# Top_Level.net
KiCad netlist of a schematic drawn in Altium Designer
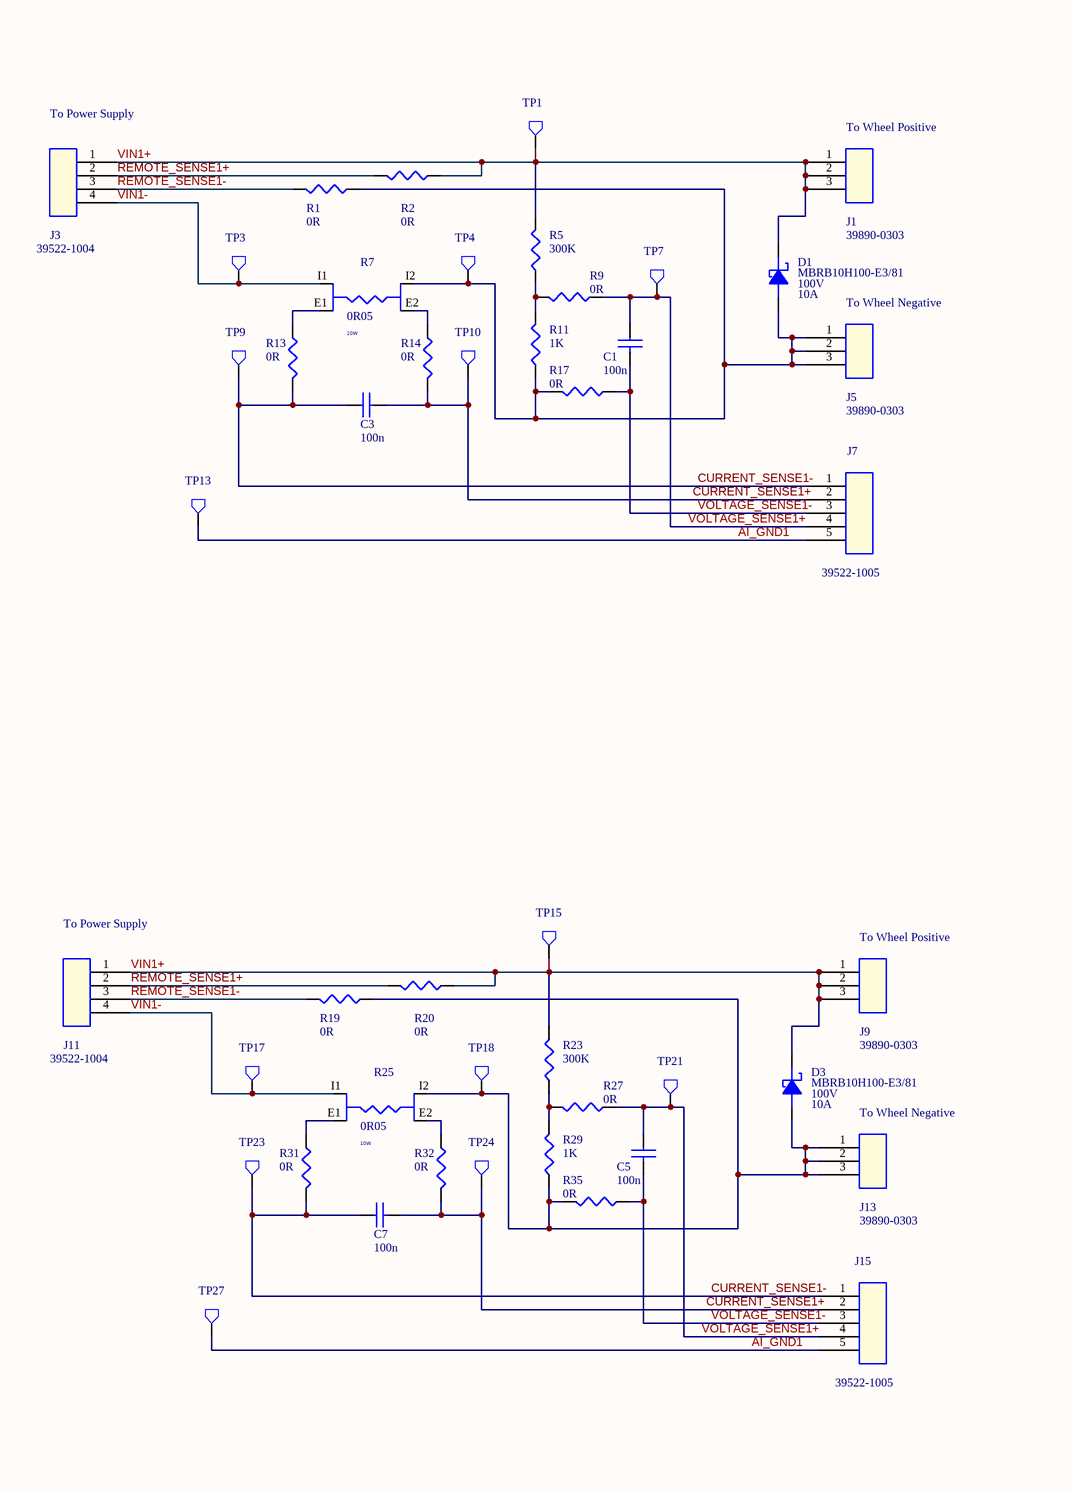
[diagram p0: Top Level.SchDoc, left]
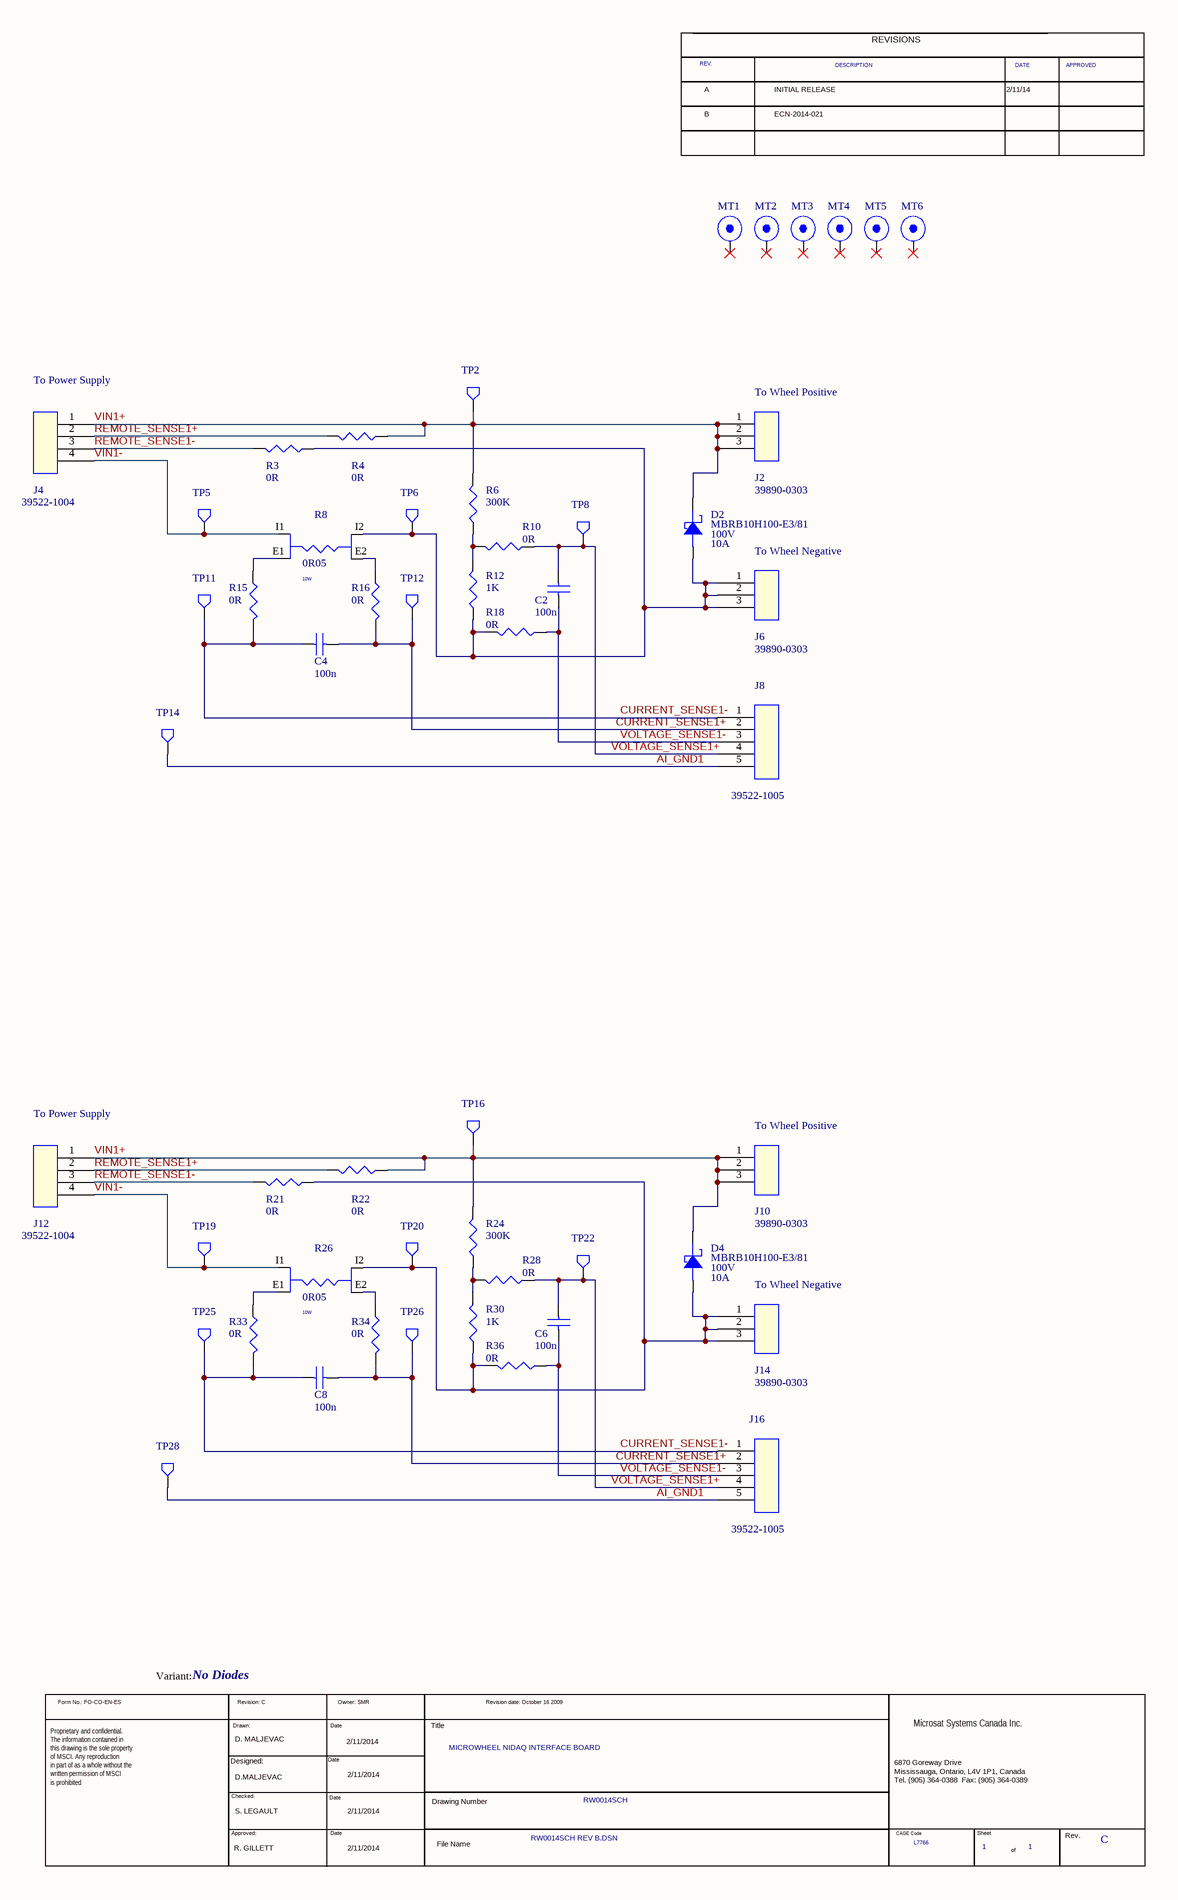
[diagram p1: Top Level.SchDoc, right]

(export (version "E")
  (design (tool "Eeschema 10.0.6"))
  (components
    (comp (ref "C1")
      (value "100n")
      (footprint "C.0805")
      (description "Film Capacitors .1uF 250volt 5%")
      (fields (field (name "PART NUMBER") "MKP1841410254") (field (name "MANUFACTURER") "Kemet"))
      (libsource (lib "*") (part "MIL-PRF-55681 - Cap, Cer"))
    )
    (comp (ref "C2")
      (value "100n")
      (footprint "C.0805")
      (description "Film Capacitors .1uF 250volt 5%")
      (fields (field (name "PART NUMBER") "MKP1841410254") (field (name "MANUFACTURER") "Kemet"))
      (libsource (lib "*") (part "MIL-PRF-55681 - Cap, Cer"))
    )
    (comp (ref "C3")
      (value "100n")
      (footprint "C.0805")
      (description "Film Capacitors .1uF 250volt 5%")
      (fields (field (name "MANUFACTURER") "Vishay") (field (name "TOLERANCE") "5%"))
      (libsource (lib "*") (part "MIL-PRF-55681 - Cap, Cer"))
    )
    (comp (ref "C4")
      (value "100n")
      (footprint "C.0805")
      (description "Film Capacitors .1uF 250volt 5%")
      (fields (field (name "MANUFACTURER") "Vishay") (field (name "TOLERANCE") "5%"))
      (libsource (lib "*") (part "MIL-PRF-55681 - Cap, Cer"))
    )
    (comp (ref "C5")
      (value "100n")
      (footprint "C.0805")
      (description "Film Capacitors .1uF 250volt 5%")
      (fields (field (name "PART NUMBER") "MKP1841410254") (field (name "MANUFACTURER") "Kemet"))
      (libsource (lib "*") (part "MIL-PRF-55681 - Cap, Cer"))
    )
    (comp (ref "C6")
      (value "100n")
      (footprint "C.0805")
      (description "Film Capacitors .1uF 250volt 5%")
      (fields (field (name "PART NUMBER") "MKP1841410254") (field (name "MANUFACTURER") "Kemet"))
      (libsource (lib "*") (part "MIL-PRF-55681 - Cap, Cer"))
    )
    (comp (ref "C7")
      (value "100n")
      (footprint "C.0805")
      (description "Film Capacitors .1uF 250volt 5%")
      (fields (field (name "MANUFACTURER") "Vishay") (field (name "TOLERANCE") "5%"))
      (libsource (lib "*") (part "MIL-PRF-55681 - Cap, Cer"))
    )
    (comp (ref "C8")
      (value "100n")
      (footprint "C.0805")
      (description "Film Capacitors .1uF 250volt 5%")
      (fields (field (name "MANUFACTURER") "Vishay") (field (name "TOLERANCE") "5%"))
      (libsource (lib "*") (part "MIL-PRF-55681 - Cap, Cer"))
    )
    (comp (ref "D1")
      (value "MBRB10H100-E3/81")
      (description "DIODE SCHOTTKY 100V 10A TO236AB")
      (fields
        (field (name "MANUFACTURER") "Vishay Semiconductor")
        (field (name "CURRENT") "10A")
        (field (name "VOLTAGE") "100V")
      )
      (libsource (lib "RW00014SCH REV B_Library") (part "DIODE SCHOTTKY"))
    )
    (comp (ref "D2")
      (value "MBRB10H100-E3/81")
      (description "DIODE SCHOTTKY 100V 10A TO236AB")
      (fields
        (field (name "MANUFACTURER") "Vishay Semiconductor")
        (field (name "CURRENT") "10A")
        (field (name "VOLTAGE") "100V")
      )
      (libsource (lib "RW00014SCH REV B_Library") (part "DIODE SCHOTTKY"))
    )
    (comp (ref "D3")
      (value "MBRB10H100-E3/81")
      (description "DIODE SCHOTTKY 100V 10A TO236AB")
      (fields
        (field (name "MANUFACTURER") "Vishay Semiconductor")
        (field (name "CURRENT") "10A")
        (field (name "VOLTAGE") "100V")
      )
      (libsource (lib "RW00014SCH REV B_Library") (part "DIODE SCHOTTKY"))
    )
    (comp (ref "D4")
      (value "MBRB10H100-E3/81")
      (description "DIODE SCHOTTKY 100V 10A TO236AB")
      (fields
        (field (name "MANUFACTURER") "Vishay Semiconductor")
        (field (name "CURRENT") "10A")
        (field (name "VOLTAGE") "100V")
      )
      (libsource (lib "RW00014SCH REV B_Library") (part "DIODE SCHOTTKY"))
    )
    (comp (ref "J1")
      (value "39890-0303")
      (footprint "CONN.39890-0303")
      (description "CONN, SCREW TERMINAL BLOCK, 3 POS, 5MM SPACING, TH")
      (fields (field (name "MANUFACTURER") "Molex"))
      (libsource (lib "*") (part "CON3"))
    )
    (comp (ref "J2")
      (value "39890-0303")
      (footprint "CONN.39890-0303")
      (description "CONN, SCREW TERMINAL BLOCK, 3 POS, 5MM SPACING, TH")
      (fields (field (name "MANUFACTURER") "Molex"))
      (libsource (lib "*") (part "CON3"))
    )
    (comp (ref "J3")
      (value "39522-1004")
      (footprint "CONN.39522-1004")
      (description "CONN, TERMINAL BLOCK HEADER, 4 POS, RIGHT ANGLE, 5MM SPACING, TH")
      (fields (field (name "MANUFACTURER") "Molex"))
      (libsource (lib "*") (part "CON4"))
    )
    (comp (ref "J4")
      (value "39522-1004")
      (footprint "CONN.39522-1004")
      (description "CONN, TERMINAL BLOCK HEADER, 4 POS, RIGHT ANGLE, 5MM SPACING, TH")
      (fields (field (name "MANUFACTURER") "Molex"))
      (libsource (lib "*") (part "CON4"))
    )
    (comp (ref "J5")
      (value "39890-0303")
      (footprint "CONN.39890-0303")
      (description "CONN, SCREW TERMINAL BLOCK, 3 POS, 5MM SPACING, TH")
      (fields (field (name "MANUFACTURER") "Molex"))
      (libsource (lib "*") (part "CON3"))
    )
    (comp (ref "J6")
      (value "39890-0303")
      (footprint "CONN.39890-0303")
      (description "CONN, SCREW TERMINAL BLOCK, 3 POS, 5MM SPACING, TH")
      (fields (field (name "MANUFACTURER") "Molex"))
      (libsource (lib "*") (part "CON3"))
    )
    (comp (ref "J7")
      (value "39522-1005")
      (footprint "CONN.39522-1005")
      (description "CONN, TERMINAL BLOCK HEADER, 5 POS, RIGHT ANGLE, 5MM SPACING, TH")
      (fields (field (name "MANUFACTURER") "Molex"))
      (libsource (lib "*") (part "CON5"))
    )
    (comp (ref "J8")
      (value "39522-1005")
      (footprint "CONN.39522-1005")
      (description "CONN, TERMINAL BLOCK HEADER, 5 POS, RIGHT ANGLE, 5MM SPACING, TH")
      (fields (field (name "MANUFACTURER") "Molex"))
      (libsource (lib "*") (part "CON5"))
    )
    (comp (ref "J9")
      (value "39890-0303")
      (footprint "CONN.39890-0303")
      (description "CONN, SCREW TERMINAL BLOCK, 3 POS, 5MM SPACING, TH")
      (fields (field (name "MANUFACTURER") "Molex"))
      (libsource (lib "*") (part "CON3"))
    )
    (comp (ref "J10")
      (value "39890-0303")
      (footprint "CONN.39890-0303")
      (description "CONN, SCREW TERMINAL BLOCK, 3 POS, 5MM SPACING, TH")
      (fields (field (name "MANUFACTURER") "Molex"))
      (libsource (lib "*") (part "CON3"))
    )
    (comp (ref "J11")
      (value "39522-1004")
      (footprint "CONN.39522-1004")
      (description "CONN, TERMINAL BLOCK HEADER, 4 POS, RIGHT ANGLE, 5MM SPACING, TH")
      (fields (field (name "MANUFACTURER") "Molex"))
      (libsource (lib "*") (part "CON4"))
    )
    (comp (ref "J12")
      (value "39522-1004")
      (footprint "CONN.39522-1004")
      (description "CONN, TERMINAL BLOCK HEADER, 4 POS, RIGHT ANGLE, 5MM SPACING, TH")
      (fields (field (name "MANUFACTURER") "Molex"))
      (libsource (lib "*") (part "CON4"))
    )
    (comp (ref "J13")
      (value "39890-0303")
      (footprint "CONN.39890-0303")
      (description "CONN, SCREW TERMINAL BLOCK, 3 POS, 5MM SPACING, TH")
      (fields (field (name "MANUFACTURER") "Molex"))
      (libsource (lib "*") (part "CON3"))
    )
    (comp (ref "J14")
      (value "39890-0303")
      (footprint "CONN.39890-0303")
      (description "CONN, SCREW TERMINAL BLOCK, 3 POS, 5MM SPACING, TH")
      (fields (field (name "MANUFACTURER") "Molex"))
      (libsource (lib "*") (part "CON3"))
    )
    (comp (ref "J15")
      (value "39522-1005")
      (footprint "CONN.39522-1005")
      (description "CONN, TERMINAL BLOCK HEADER, 5 POS, RIGHT ANGLE, 5MM SPACING, TH")
      (fields (field (name "MANUFACTURER") "Molex"))
      (libsource (lib "*") (part "CON5"))
    )
    (comp (ref "J16")
      (value "39522-1005")
      (footprint "CONN.39522-1005")
      (description "CONN, TERMINAL BLOCK HEADER, 5 POS, RIGHT ANGLE, 5MM SPACING, TH")
      (fields (field (name "MANUFACTURER") "Molex"))
      (libsource (lib "*") (part "CON5"))
    )
    (comp (ref "MT1")
      (value "MOUNTING_HOLE")
      (footprint "see guidelines")
      (description "MOUNTING HOLE, PLATED TH, 0.150\" HOLE, 0.350\" DIAMETER, TH")
      (libsource (lib "*") (part "MOUNTING_HOLE"))
    )
    (comp (ref "MT2")
      (value "MOUNTING_HOLE")
      (footprint "see guidelines")
      (description "MOUNTING HOLE, PLATED TH, 0.150\" HOLE, 0.350\" DIAMETER, TH")
      (libsource (lib "*") (part "MOUNTING_HOLE"))
    )
    (comp (ref "MT3")
      (value "MOUNTING_HOLE")
      (footprint "see guidelines")
      (description "MOUNTING HOLE, PLATED TH, 0.150\" HOLE, 0.350\" DIAMETER, TH")
      (libsource (lib "*") (part "MOUNTING_HOLE"))
    )
    (comp (ref "MT4")
      (value "MOUNTING_HOLE")
      (footprint "see guidelines")
      (description "MOUNTING HOLE, PLATED TH, 0.150\" HOLE, 0.350\" DIAMETER, TH")
      (libsource (lib "*") (part "MOUNTING_HOLE"))
    )
    (comp (ref "MT5")
      (value "MOUNTING_HOLE")
      (footprint "see guidelines")
      (description "MOUNTING HOLE, PLATED TH, 0.150\" HOLE, 0.350\" DIAMETER, TH")
      (libsource (lib "*") (part "MOUNTING_HOLE"))
    )
    (comp (ref "MT6")
      (value "MOUNTING_HOLE")
      (footprint "see guidelines")
      (description "MOUNTING HOLE, PLATED TH, 0.150\" HOLE, 0.350\" DIAMETER, TH")
      (libsource (lib "*") (part "MOUNTING_HOLE"))
    )
    (comp (ref "R1")
      (value "0R")
      (footprint "R.0805")
      (description "RES, 0R0, 0W125, 0805")
      (fields (field (name "POWER") "0W125") (field (name "MANUFACTURER") "Panasonic"))
      (libsource (lib "*") (part "MIL-PRF-55342 - Res, Chip_0"))
    )
    (comp (ref "R2")
      (value "0R")
      (footprint "R.0805")
      (description "RES, 0R0, 0W125, 0805")
      (fields (field (name "POWER") "0W125") (field (name "MANUFACTURER") "Panasonic"))
      (libsource (lib "*") (part "MIL-PRF-55342 - Res, Chip_0"))
    )
    (comp (ref "R3")
      (value "0R")
      (footprint "R.0805")
      (description "RES, 0R0, 0W125, 0805")
      (fields (field (name "POWER") "0W125") (field (name "MANUFACTURER") "Panasonic"))
      (libsource (lib "*") (part "MIL-PRF-55342 - Res, Chip_0"))
    )
    (comp (ref "R4")
      (value "0R")
      (footprint "R.0805")
      (description "RES, 0R0, 0W125, 0805")
      (fields (field (name "POWER") "0W125") (field (name "MANUFACTURER") "Panasonic"))
      (libsource (lib "*") (part "MIL-PRF-55342 - Res, Chip_0"))
    )
    (comp (ref "R5")
      (value "300K")
      (footprint "R.1206")
      (description "RES, 300K0, 0.1%, 0W125, 1206")
      (fields (field (name "TOLERANCE") "0%1") (field (name "PART NUMBER") "ERA-8AEB304V"))
      (libsource (lib "*") (part "MIL-PRF-55342 - Res, Chip_0"))
    )
    (comp (ref "R6")
      (value "300K")
      (footprint "R.1206")
      (description "RES, 300K0, 0.1%, 0W125, 1206")
      (fields (field (name "TOLERANCE") "0%1") (field (name "PART NUMBER") "ERA-8AEB304V"))
      (libsource (lib "*") (part "MIL-PRF-55342 - Res, Chip_0"))
    )
    (comp (ref "R7")
      (value "0R05")
      (footprint "TBD")
      (description "RES, 0R05, 0.1%, 2W, 3637")
      (fields
        (field (name "MANUFACTURER") "Ohmite")
        (field (name "POWER") "10W")
        (field (name "TOLERANCE") "0.1%")
      )
      (libsource (lib "*") (part "LVK24_RES_2"))
    )
    (comp (ref "R8")
      (value "0R05")
      (footprint "TBD")
      (description "RES, 0R05, 0.1%, 2W, 3637")
      (fields
        (field (name "MANUFACTURER") "Ohmite")
        (field (name "POWER") "10W")
        (field (name "TOLERANCE") "0.1%")
      )
      (libsource (lib "*") (part "LVK24_RES_2"))
    )
    (comp (ref "R9")
      (value "0R")
      (footprint "R.0805")
      (description "RES, 0R0, 0W125, 0805")
      (fields (field (name "POWER") "0W125") (field (name "MANUFACTURER") "Panasonic"))
      (libsource (lib "*") (part "MIL-PRF-55342 - Res, Chip_0"))
    )
    (comp (ref "R10")
      (value "0R")
      (footprint "R.0805")
      (description "RES, 0R0, 0W125, 0805")
      (fields (field (name "POWER") "0W125") (field (name "MANUFACTURER") "Panasonic"))
      (libsource (lib "*") (part "MIL-PRF-55342 - Res, Chip_0"))
    )
    (comp (ref "R11")
      (value "1K")
      (footprint "R.1206")
      (description "RES, 1K0, 0.1%, 1W0, 1206")
      (fields
        (field (name "MANUFACTURER") "Vishay Thin Film")
        (field (name "PART NUMBER") "PHP01206E1001BST5")
      )
      (libsource (lib "*") (part "MIL-PRF-55342 - Res, Chip_0"))
    )
    (comp (ref "R12")
      (value "1K")
      (footprint "R.1206")
      (description "RES, 1K0, 0.1%, 1W0, 1206")
      (fields
        (field (name "MANUFACTURER") "Vishay Thin Film")
        (field (name "PART NUMBER") "PHP01206E1001BST5")
      )
      (libsource (lib "*") (part "MIL-PRF-55342 - Res, Chip_0"))
    )
    (comp (ref "R13")
      (value "0R")
      (footprint "R.0805")
      (description "RES, 0R0, 0W125, 0805")
      (fields (field (name "POWER") "0W125") (field (name "MANUFACTURER") "Panasonic"))
      (libsource (lib "*") (part "MIL-PRF-55342 - Res, Chip_0"))
    )
    (comp (ref "R14")
      (value "0R")
      (footprint "R.0805")
      (description "RES, 0R0, 0W125, 0805")
      (fields (field (name "POWER") "0W125") (field (name "MANUFACTURER") "Panasonic"))
      (libsource (lib "*") (part "MIL-PRF-55342 - Res, Chip_0"))
    )
    (comp (ref "R15")
      (value "0R")
      (footprint "R.0805")
      (description "RES, 0R0, 0W125, 0805")
      (fields (field (name "POWER") "0W125") (field (name "MANUFACTURER") "Panasonic"))
      (libsource (lib "*") (part "MIL-PRF-55342 - Res, Chip_0"))
    )
    (comp (ref "R16")
      (value "0R")
      (footprint "R.0805")
      (description "RES, 0R0, 0W125, 0805")
      (fields (field (name "POWER") "0W125") (field (name "MANUFACTURER") "Panasonic"))
      (libsource (lib "*") (part "MIL-PRF-55342 - Res, Chip_0"))
    )
    (comp (ref "R17")
      (value "0R")
      (footprint "R.0805")
      (description "RES, 0R0, 0W125, 0805")
      (fields (field (name "POWER") "0W125") (field (name "MANUFACTURER") "Panasonic"))
      (libsource (lib "*") (part "MIL-PRF-55342 - Res, Chip_0"))
    )
    (comp (ref "R18")
      (value "0R")
      (footprint "R.0805")
      (description "RES, 0R0, 0W125, 0805")
      (fields (field (name "POWER") "0W125") (field (name "MANUFACTURER") "Panasonic"))
      (libsource (lib "*") (part "MIL-PRF-55342 - Res, Chip_0"))
    )
    (comp (ref "R19")
      (value "0R")
      (footprint "R.0805")
      (description "RES, 0R0, 0W125, 0805")
      (fields (field (name "POWER") "0W125") (field (name "MANUFACTURER") "Panasonic"))
      (libsource (lib "*") (part "MIL-PRF-55342 - Res, Chip_0"))
    )
    (comp (ref "R20")
      (value "0R")
      (footprint "R.0805")
      (description "RES, 0R0, 0W125, 0805")
      (fields (field (name "POWER") "0W125") (field (name "MANUFACTURER") "Panasonic"))
      (libsource (lib "*") (part "MIL-PRF-55342 - Res, Chip_0"))
    )
    (comp (ref "R21")
      (value "0R")
      (footprint "R.0805")
      (description "RES, 0R0, 0W125, 0805")
      (fields (field (name "POWER") "0W125") (field (name "MANUFACTURER") "Panasonic"))
      (libsource (lib "*") (part "MIL-PRF-55342 - Res, Chip_0"))
    )
    (comp (ref "R22")
      (value "0R")
      (footprint "R.0805")
      (description "RES, 0R0, 0W125, 0805")
      (fields (field (name "POWER") "0W125") (field (name "MANUFACTURER") "Panasonic"))
      (libsource (lib "*") (part "MIL-PRF-55342 - Res, Chip_0"))
    )
    (comp (ref "R23")
      (value "300K")
      (footprint "R.1206")
      (description "RES, 300K0, 0.1%, 0W125, 1206")
      (fields (field (name "TOLERANCE") "0%1") (field (name "PART NUMBER") "ERA-8AEB304V"))
      (libsource (lib "*") (part "MIL-PRF-55342 - Res, Chip_0"))
    )
    (comp (ref "R24")
      (value "300K")
      (footprint "R.1206")
      (description "RES, 300K0, 0.1%, 0W125, 1206")
      (fields (field (name "TOLERANCE") "0%1") (field (name "PART NUMBER") "ERA-8AEB304V"))
      (libsource (lib "*") (part "MIL-PRF-55342 - Res, Chip_0"))
    )
    (comp (ref "R25")
      (value "0R05")
      (footprint "TBD")
      (description "RES, 0R05, 0.1%, 2W, 3637")
      (fields
        (field (name "MANUFACTURER") "Ohmite")
        (field (name "POWER") "10W")
        (field (name "TOLERANCE") "0.1%")
      )
      (libsource (lib "*") (part "LVK24_RES_2"))
    )
    (comp (ref "R26")
      (value "0R05")
      (footprint "TBD")
      (description "RES, 0R05, 0.1%, 2W, 3637")
      (fields
        (field (name "MANUFACTURER") "Ohmite")
        (field (name "POWER") "10W")
        (field (name "TOLERANCE") "0.1%")
      )
      (libsource (lib "*") (part "LVK24_RES_2"))
    )
    (comp (ref "R27")
      (value "0R")
      (footprint "R.0805")
      (description "RES, 0R0, 0W125, 0805")
      (fields (field (name "POWER") "0W125") (field (name "MANUFACTURER") "Panasonic"))
      (libsource (lib "*") (part "MIL-PRF-55342 - Res, Chip_0"))
    )
    (comp (ref "R28")
      (value "0R")
      (footprint "R.0805")
      (description "RES, 0R0, 0W125, 0805")
      (fields (field (name "POWER") "0W125") (field (name "MANUFACTURER") "Panasonic"))
      (libsource (lib "*") (part "MIL-PRF-55342 - Res, Chip_0"))
    )
    (comp (ref "R29")
      (value "1K")
      (footprint "R.1206")
      (description "RES, 1K0, 0.1%, 1W0, 1206")
      (fields
        (field (name "MANUFACTURER") "Vishay Thin Film")
        (field (name "PART NUMBER") "PHP01206E1001BST5")
      )
      (libsource (lib "*") (part "MIL-PRF-55342 - Res, Chip_0"))
    )
    (comp (ref "R30")
      (value "1K")
      (footprint "R.1206")
      (description "RES, 1K0, 0.1%, 1W0, 1206")
      (fields
        (field (name "MANUFACTURER") "Vishay Thin Film")
        (field (name "PART NUMBER") "PHP01206E1001BST5")
      )
      (libsource (lib "*") (part "MIL-PRF-55342 - Res, Chip_0"))
    )
    (comp (ref "R31")
      (value "0R")
      (footprint "R.0805")
      (description "RES, 0R0, 0W125, 0805")
      (fields (field (name "POWER") "0W125") (field (name "MANUFACTURER") "Panasonic"))
      (libsource (lib "*") (part "MIL-PRF-55342 - Res, Chip_0"))
    )
    (comp (ref "R32")
      (value "0R")
      (footprint "R.0805")
      (description "RES, 0R0, 0W125, 0805")
      (fields (field (name "POWER") "0W125") (field (name "MANUFACTURER") "Panasonic"))
      (libsource (lib "*") (part "MIL-PRF-55342 - Res, Chip_0"))
    )
    (comp (ref "R33")
      (value "0R")
      (footprint "R.0805")
      (description "RES, 0R0, 0W125, 0805")
      (fields (field (name "POWER") "0W125") (field (name "MANUFACTURER") "Panasonic"))
      (libsource (lib "*") (part "MIL-PRF-55342 - Res, Chip_0"))
    )
    (comp (ref "R34")
      (value "0R")
      (footprint "R.0805")
      (description "RES, 0R0, 0W125, 0805")
      (fields (field (name "POWER") "0W125") (field (name "MANUFACTURER") "Panasonic"))
      (libsource (lib "*") (part "MIL-PRF-55342 - Res, Chip_0"))
    )
    (comp (ref "R35")
      (value "0R")
      (footprint "R.0805")
      (description "RES, 0R0, 0W125, 0805")
      (fields (field (name "POWER") "0W125") (field (name "MANUFACTURER") "Panasonic"))
      (libsource (lib "*") (part "MIL-PRF-55342 - Res, Chip_0"))
    )
    (comp (ref "R36")
      (value "0R")
      (footprint "R.0805")
      (description "RES, 0R0, 0W125, 0805")
      (fields (field (name "POWER") "0W125") (field (name "MANUFACTURER") "Panasonic"))
      (libsource (lib "*") (part "MIL-PRF-55342 - Res, Chip_0"))
    )
    (comp (ref "TP1")
      (value "TEST POINT")
      (footprint "TH.0.063\"")
      (description "TEST POINT, RED, COMPACT PC, LOOP, 0.125\" DIAMETER, TH.0.063\"")
      (fields (field (name "MANUFACTURER") "Keystone Electronics") (field (name "PART NUMBER") "5005"))
      (libsource (lib "*") (part "TEST POINT"))
    )
    (comp (ref "TP2")
      (value "TEST POINT")
      (footprint "TH.0.063\"")
      (description "TEST POINT, RED, COMPACT PC, LOOP, 0.125\" DIAMETER, TH.0.063\"")
      (fields (field (name "MANUFACTURER") "Keystone Electronics") (field (name "PART NUMBER") "5005"))
      (libsource (lib "*") (part "TEST POINT"))
    )
    (comp (ref "TP3")
      (value "TEST POINT")
      (footprint "TH.0.063\"")
      (description "TEST POINT, RED, COMPACT PC, LOOP, 0.125\" DIAMETER, TH.0.063\"")
      (fields (field (name "PART NUMBER") "5005") (field (name "MANUFACTURER") "Keystone Electronics"))
      (libsource (lib "*") (part "TEST POINT"))
    )
    (comp (ref "TP4")
      (value "TEST POINT")
      (footprint "TH.0.063\"")
      (description "TEST POINT, RED, COMPACT PC, LOOP, 0.125\" DIAMETER, TH.0.063\"")
      (fields (field (name "PART NUMBER") "5005") (field (name "MANUFACTURER") "Keystone Electronics"))
      (libsource (lib "*") (part "TEST POINT"))
    )
    (comp (ref "TP5")
      (value "TEST POINT")
      (footprint "TH.0.063\"")
      (description "TEST POINT, RED, COMPACT PC, LOOP, 0.125\" DIAMETER, TH.0.063\"")
      (fields (field (name "PART NUMBER") "5005") (field (name "MANUFACTURER") "Keystone Electronics"))
      (libsource (lib "*") (part "TEST POINT"))
    )
    (comp (ref "TP6")
      (value "TEST POINT")
      (footprint "TH.0.063\"")
      (description "TEST POINT, RED, COMPACT PC, LOOP, 0.125\" DIAMETER, TH.0.063\"")
      (fields (field (name "PART NUMBER") "5005") (field (name "MANUFACTURER") "Keystone Electronics"))
      (libsource (lib "*") (part "TEST POINT"))
    )
    (comp (ref "TP7")
      (value "TEST POINT")
      (footprint "TH.0.063\"")
      (description "TEST POINT, RED, COMPACT PC, LOOP, 0.125\" DIAMETER, TH.0.063\"")
      (fields (field (name "MANUFACTURER") "Keystone Electronics") (field (name "PART NUMBER") "5005"))
      (libsource (lib "*") (part "TEST POINT"))
    )
    (comp (ref "TP8")
      (value "TEST POINT")
      (footprint "TH.0.063\"")
      (description "TEST POINT, RED, COMPACT PC, LOOP, 0.125\" DIAMETER, TH.0.063\"")
      (fields (field (name "MANUFACTURER") "Keystone Electronics") (field (name "PART NUMBER") "5005"))
      (libsource (lib "*") (part "TEST POINT"))
    )
    (comp (ref "TP9")
      (value "TEST POINT")
      (footprint "TH.0.063\"")
      (description "TEST POINT, RED, COMPACT PC, LOOP, 0.125\" DIAMETER, TH.0.063\"")
      (fields (field (name "PART NUMBER") "5005") (field (name "MANUFACTURER") "Keystone Electronics"))
      (libsource (lib "*") (part "TEST POINT"))
    )
    (comp (ref "TP10")
      (value "TEST POINT")
      (footprint "TH.0.063\"")
      (description "TEST POINT, RED, COMPACT PC, LOOP, 0.125\" DIAMETER, TH.0.063\"")
      (fields (field (name "MANUFACTURER") "Keystone Electronics") (field (name "PART NUMBER") "5005"))
      (libsource (lib "*") (part "TEST POINT"))
    )
    (comp (ref "TP11")
      (value "TEST POINT")
      (footprint "TH.0.063\"")
      (description "TEST POINT, RED, COMPACT PC, LOOP, 0.125\" DIAMETER, TH.0.063\"")
      (fields (field (name "PART NUMBER") "5005") (field (name "MANUFACTURER") "Keystone Electronics"))
      (libsource (lib "*") (part "TEST POINT"))
    )
    (comp (ref "TP12")
      (value "TEST POINT")
      (footprint "TH.0.063\"")
      (description "TEST POINT, RED, COMPACT PC, LOOP, 0.125\" DIAMETER, TH.0.063\"")
      (fields (field (name "MANUFACTURER") "Keystone Electronics") (field (name "PART NUMBER") "5005"))
      (libsource (lib "*") (part "TEST POINT"))
    )
    (comp (ref "TP13")
      (value "TEST POINT")
      (footprint "TH.0.063\"")
      (description "TEST POINT, RED, COMPACT PC, LOOP, 0.125\" DIAMETER, TH.0.063\"")
      (fields (field (name "PART NUMBER") "5005") (field (name "MANUFACTURER") "Keystone Electronics"))
      (libsource (lib "*") (part "TEST POINT"))
    )
    (comp (ref "TP14")
      (value "TEST POINT")
      (footprint "TH.0.063\"")
      (description "TEST POINT, RED, COMPACT PC, LOOP, 0.125\" DIAMETER, TH.0.063\"")
      (fields (field (name "PART NUMBER") "5005") (field (name "MANUFACTURER") "Keystone Electronics"))
      (libsource (lib "*") (part "TEST POINT"))
    )
    (comp (ref "TP15")
      (value "TEST POINT")
      (footprint "TH.0.063\"")
      (description "TEST POINT, RED, COMPACT PC, LOOP, 0.125\" DIAMETER, TH.0.063\"")
      (fields (field (name "MANUFACTURER") "Keystone Electronics") (field (name "PART NUMBER") "5005"))
      (libsource (lib "*") (part "TEST POINT"))
    )
    (comp (ref "TP16")
      (value "TEST POINT")
      (footprint "TH.0.063\"")
      (description "TEST POINT, RED, COMPACT PC, LOOP, 0.125\" DIAMETER, TH.0.063\"")
      (fields (field (name "MANUFACTURER") "Keystone Electronics") (field (name "PART NUMBER") "5005"))
      (libsource (lib "*") (part "TEST POINT"))
    )
    (comp (ref "TP17")
      (value "TEST POINT")
      (footprint "TH.0.063\"")
      (description "TEST POINT, RED, COMPACT PC, LOOP, 0.125\" DIAMETER, TH.0.063\"")
      (fields (field (name "PART NUMBER") "5005") (field (name "MANUFACTURER") "Keystone Electronics"))
      (libsource (lib "*") (part "TEST POINT"))
    )
    (comp (ref "TP18")
      (value "TEST POINT")
      (footprint "TH.0.063\"")
      (description "TEST POINT, RED, COMPACT PC, LOOP, 0.125\" DIAMETER, TH.0.063\"")
      (fields (field (name "PART NUMBER") "5005") (field (name "MANUFACTURER") "Keystone Electronics"))
      (libsource (lib "*") (part "TEST POINT"))
    )
    (comp (ref "TP19")
      (value "TEST POINT")
      (footprint "TH.0.063\"")
      (description "TEST POINT, RED, COMPACT PC, LOOP, 0.125\" DIAMETER, TH.0.063\"")
      (fields (field (name "PART NUMBER") "5005") (field (name "MANUFACTURER") "Keystone Electronics"))
      (libsource (lib "*") (part "TEST POINT"))
    )
    (comp (ref "TP20")
      (value "TEST POINT")
      (footprint "TH.0.063\"")
      (description "TEST POINT, RED, COMPACT PC, LOOP, 0.125\" DIAMETER, TH.0.063\"")
      (fields (field (name "PART NUMBER") "5005") (field (name "MANUFACTURER") "Keystone Electronics"))
      (libsource (lib "*") (part "TEST POINT"))
    )
    (comp (ref "TP21")
      (value "TEST POINT")
      (footprint "TH.0.063\"")
      (description "TEST POINT, RED, COMPACT PC, LOOP, 0.125\" DIAMETER, TH.0.063\"")
      (fields (field (name "MANUFACTURER") "Keystone Electronics") (field (name "PART NUMBER") "5005"))
      (libsource (lib "*") (part "TEST POINT"))
    )
    (comp (ref "TP22")
      (value "TEST POINT")
      (footprint "TH.0.063\"")
      (description "TEST POINT, RED, COMPACT PC, LOOP, 0.125\" DIAMETER, TH.0.063\"")
      (fields (field (name "MANUFACTURER") "Keystone Electronics") (field (name "PART NUMBER") "5005"))
      (libsource (lib "*") (part "TEST POINT"))
    )
    (comp (ref "TP23")
      (value "TEST POINT")
      (footprint "TH.0.063\"")
      (description "TEST POINT, RED, COMPACT PC, LOOP, 0.125\" DIAMETER, TH.0.063\"")
      (fields (field (name "PART NUMBER") "5005") (field (name "MANUFACTURER") "Keystone Electronics"))
      (libsource (lib "*") (part "TEST POINT"))
    )
    (comp (ref "TP24")
      (value "TEST POINT")
      (footprint "TH.0.063\"")
      (description "TEST POINT, RED, COMPACT PC, LOOP, 0.125\" DIAMETER, TH.0.063\"")
      (fields (field (name "MANUFACTURER") "Keystone Electronics") (field (name "PART NUMBER") "5005"))
      (libsource (lib "*") (part "TEST POINT"))
    )
    (comp (ref "TP25")
      (value "TEST POINT")
      (footprint "TH.0.063\"")
      (description "TEST POINT, RED, COMPACT PC, LOOP, 0.125\" DIAMETER, TH.0.063\"")
      (fields (field (name "PART NUMBER") "5005") (field (name "MANUFACTURER") "Keystone Electronics"))
      (libsource (lib "*") (part "TEST POINT"))
    )
    (comp (ref "TP26")
      (value "TEST POINT")
      (footprint "TH.0.063\"")
      (description "TEST POINT, RED, COMPACT PC, LOOP, 0.125\" DIAMETER, TH.0.063\"")
      (fields (field (name "MANUFACTURER") "Keystone Electronics") (field (name "PART NUMBER") "5005"))
      (libsource (lib "*") (part "TEST POINT"))
    )
    (comp (ref "TP27")
      (value "TEST POINT")
      (footprint "TH.0.063\"")
      (description "TEST POINT, RED, COMPACT PC, LOOP, 0.125\" DIAMETER, TH.0.063\"")
      (fields (field (name "PART NUMBER") "5005") (field (name "MANUFACTURER") "Keystone Electronics"))
      (libsource (lib "*") (part "TEST POINT"))
    )
    (comp (ref "TP28")
      (value "TEST POINT")
      (footprint "TH.0.063\"")
      (description "TEST POINT, RED, COMPACT PC, LOOP, 0.125\" DIAMETER, TH.0.063\"")
      (fields (field (name "PART NUMBER") "5005") (field (name "MANUFACTURER") "Keystone Electronics"))
      (libsource (lib "*") (part "TEST POINT"))
    )
  )
  (nets
    (net (code "1") (name "/AI_GND1") (class "Default")
      (node (ref "J15") (pin "5") (pinfunction "5_5") (pintype "passive"))
      (node (ref "J16") (pin "5") (pinfunction "5_5") (pintype "passive"))
      (node (ref "J7") (pin "5") (pinfunction "5_5") (pintype "passive"))
      (node (ref "J8") (pin "5") (pinfunction "5_5") (pintype "passive"))
      (node (ref "TP13") (pin "1") (pinfunction "TP_1") (pintype "passive"))
      (node (ref "TP14") (pin "1") (pinfunction "TP_1") (pintype "passive"))
      (node (ref "TP27") (pin "1") (pinfunction "TP_1") (pintype "passive"))
      (node (ref "TP28") (pin "1") (pinfunction "TP_1") (pintype "passive"))
    )
    (net (code "2") (name "/CURRENT_SENSE1+") (class "Default")
      (node (ref "C3") (pin "2") (pinfunction "2_2") (pintype "passive"))
      (node (ref "C4") (pin "2") (pinfunction "2_2") (pintype "passive"))
      (node (ref "C7") (pin "2") (pinfunction "2_2") (pintype "passive"))
      (node (ref "C8") (pin "2") (pinfunction "2_2") (pintype "passive"))
      (node (ref "J15") (pin "2") (pinfunction "2_2") (pintype "passive"))
      (node (ref "J16") (pin "2") (pinfunction "2_2") (pintype "passive"))
      (node (ref "J7") (pin "2") (pinfunction "2_2") (pintype "passive"))
      (node (ref "J8") (pin "2") (pinfunction "2_2") (pintype "passive"))
      (node (ref "R14") (pin "2") (pinfunction "2_2") (pintype "passive"))
      (node (ref "R16") (pin "2") (pinfunction "2_2") (pintype "passive"))
      (node (ref "R32") (pin "2") (pinfunction "2_2") (pintype "passive"))
      (node (ref "R34") (pin "2") (pinfunction "2_2") (pintype "passive"))
      (node (ref "TP10") (pin "1") (pinfunction "TP_1") (pintype "passive"))
      (node (ref "TP12") (pin "1") (pinfunction "TP_1") (pintype "passive"))
      (node (ref "TP24") (pin "1") (pinfunction "TP_1") (pintype "passive"))
      (node (ref "TP26") (pin "1") (pinfunction "TP_1") (pintype "passive"))
    )
    (net (code "3") (name "/CURRENT_SENSE1-") (class "Default")
      (node (ref "C3") (pin "1") (pinfunction "1_1") (pintype "passive"))
      (node (ref "C4") (pin "1") (pinfunction "1_1") (pintype "passive"))
      (node (ref "C7") (pin "1") (pinfunction "1_1") (pintype "passive"))
      (node (ref "C8") (pin "1") (pinfunction "1_1") (pintype "passive"))
      (node (ref "J15") (pin "1") (pinfunction "1_1") (pintype "passive"))
      (node (ref "J16") (pin "1") (pinfunction "1_1") (pintype "passive"))
      (node (ref "J7") (pin "1") (pinfunction "1_1") (pintype "passive"))
      (node (ref "J8") (pin "1") (pinfunction "1_1") (pintype "passive"))
      (node (ref "R13") (pin "2") (pinfunction "2_2") (pintype "passive"))
      (node (ref "R15") (pin "2") (pinfunction "2_2") (pintype "passive"))
      (node (ref "R31") (pin "2") (pinfunction "2_2") (pintype "passive"))
      (node (ref "R33") (pin "2") (pinfunction "2_2") (pintype "passive"))
      (node (ref "TP11") (pin "1") (pinfunction "TP_1") (pintype "passive"))
      (node (ref "TP23") (pin "1") (pinfunction "TP_1") (pintype "passive"))
      (node (ref "TP25") (pin "1") (pinfunction "TP_1") (pintype "passive"))
      (node (ref "TP9") (pin "1") (pinfunction "TP_1") (pintype "passive"))
    )
    (net (code "4") (name "/REMOTE_SENSE1+") (class "Default")
      (node (ref "J11") (pin "2") (pinfunction "2_2") (pintype "passive"))
      (node (ref "J12") (pin "2") (pinfunction "2_2") (pintype "passive"))
      (node (ref "J3") (pin "2") (pinfunction "2_2") (pintype "passive"))
      (node (ref "J4") (pin "2") (pinfunction "2_2") (pintype "passive"))
      (node (ref "R2") (pin "2") (pinfunction "2_2") (pintype "passive"))
      (node (ref "R20") (pin "2") (pinfunction "2_2") (pintype "passive"))
      (node (ref "R22") (pin "2") (pinfunction "2_2") (pintype "passive"))
      (node (ref "R4") (pin "2") (pinfunction "2_2") (pintype "passive"))
    )
    (net (code "5") (name "/REMOTE_SENSE1-") (class "Default")
      (node (ref "J11") (pin "3") (pinfunction "3_3") (pintype "passive"))
      (node (ref "J12") (pin "3") (pinfunction "3_3") (pintype "passive"))
      (node (ref "J3") (pin "3") (pinfunction "3_3") (pintype "passive"))
      (node (ref "J4") (pin "3") (pinfunction "3_3") (pintype "passive"))
      (node (ref "R1") (pin "2") (pinfunction "2_2") (pintype "passive"))
      (node (ref "R19") (pin "2") (pinfunction "2_2") (pintype "passive"))
      (node (ref "R21") (pin "2") (pinfunction "2_2") (pintype "passive"))
      (node (ref "R3") (pin "2") (pinfunction "2_2") (pintype "passive"))
    )
    (net (code "6") (name "/VIN1+") (class "Default")
      (node (ref "D1") (pin "K") (pinfunction "CATHODE_K") (pintype "passive"))
      (node (ref "D2") (pin "K") (pinfunction "CATHODE_K") (pintype "passive"))
      (node (ref "D3") (pin "K") (pinfunction "CATHODE_K") (pintype "passive"))
      (node (ref "D4") (pin "K") (pinfunction "CATHODE_K") (pintype "passive"))
      (node (ref "J1") (pin "1") (pinfunction "1_1") (pintype "passive"))
      (node (ref "J1") (pin "2") (pinfunction "2_2") (pintype "passive"))
      (node (ref "J1") (pin "3") (pinfunction "3_3") (pintype "passive"))
      (node (ref "J10") (pin "1") (pinfunction "1_1") (pintype "passive"))
      (node (ref "J10") (pin "2") (pinfunction "2_2") (pintype "passive"))
      (node (ref "J10") (pin "3") (pinfunction "3_3") (pintype "passive"))
      (node (ref "J11") (pin "1") (pinfunction "1_1") (pintype "passive"))
      (node (ref "J12") (pin "1") (pinfunction "1_1") (pintype "passive"))
      (node (ref "J2") (pin "1") (pinfunction "1_1") (pintype "passive"))
      (node (ref "J2") (pin "2") (pinfunction "2_2") (pintype "passive"))
      (node (ref "J2") (pin "3") (pinfunction "3_3") (pintype "passive"))
      (node (ref "J3") (pin "1") (pinfunction "1_1") (pintype "passive"))
      (node (ref "J4") (pin "1") (pinfunction "1_1") (pintype "passive"))
      (node (ref "J9") (pin "1") (pinfunction "1_1") (pintype "passive"))
      (node (ref "J9") (pin "2") (pinfunction "2_2") (pintype "passive"))
      (node (ref "J9") (pin "3") (pinfunction "3_3") (pintype "passive"))
      (node (ref "R2") (pin "1") (pinfunction "1_1") (pintype "passive"))
      (node (ref "R20") (pin "1") (pinfunction "1_1") (pintype "passive"))
      (node (ref "R22") (pin "1") (pinfunction "1_1") (pintype "passive"))
      (node (ref "R23") (pin "2") (pinfunction "2_2") (pintype "passive"))
      (node (ref "R24") (pin "2") (pinfunction "2_2") (pintype "passive"))
      (node (ref "R4") (pin "1") (pinfunction "1_1") (pintype "passive"))
      (node (ref "R5") (pin "2") (pinfunction "2_2") (pintype "passive"))
      (node (ref "R6") (pin "2") (pinfunction "2_2") (pintype "passive"))
      (node (ref "TP1") (pin "1") (pinfunction "TP_1") (pintype "passive"))
      (node (ref "TP15") (pin "1") (pinfunction "TP_1") (pintype "passive"))
      (node (ref "TP16") (pin "1") (pinfunction "TP_1") (pintype "passive"))
      (node (ref "TP2") (pin "1") (pinfunction "TP_1") (pintype "passive"))
    )
    (net (code "7") (name "/VIN1-") (class "Default")
      (node (ref "J11") (pin "4") (pinfunction "4_4") (pintype "passive"))
      (node (ref "J12") (pin "4") (pinfunction "4_4") (pintype "passive"))
      (node (ref "J3") (pin "4") (pinfunction "4_4") (pintype "passive"))
      (node (ref "J4") (pin "4") (pinfunction "4_4") (pintype "passive"))
      (node (ref "R25") (pin "I1") (pinfunction "I1_I1") (pintype "passive"))
      (node (ref "R26") (pin "I1") (pinfunction "I1_I1") (pintype "passive"))
      (node (ref "R7") (pin "I1") (pinfunction "I1_I1") (pintype "passive"))
      (node (ref "R8") (pin "I1") (pinfunction "I1_I1") (pintype "passive"))
      (node (ref "TP17") (pin "1") (pinfunction "TP_1") (pintype "passive"))
      (node (ref "TP19") (pin "1") (pinfunction "TP_1") (pintype "passive"))
      (node (ref "TP3") (pin "1") (pinfunction "TP_1") (pintype "passive"))
      (node (ref "TP5") (pin "1") (pinfunction "TP_1") (pintype "passive"))
    )
    (net (code "8") (name "/VOLTAGE_SENSE1+") (class "Default")
      (node (ref "C1") (pin "1") (pinfunction "1_1") (pintype "passive"))
      (node (ref "C2") (pin "1") (pinfunction "1_1") (pintype "passive"))
      (node (ref "C5") (pin "1") (pinfunction "1_1") (pintype "passive"))
      (node (ref "C6") (pin "1") (pinfunction "1_1") (pintype "passive"))
      (node (ref "J15") (pin "4") (pinfunction "4_4") (pintype "passive"))
      (node (ref "J16") (pin "4") (pinfunction "4_4") (pintype "passive"))
      (node (ref "J7") (pin "4") (pinfunction "4_4") (pintype "passive"))
      (node (ref "J8") (pin "4") (pinfunction "4_4") (pintype "passive"))
      (node (ref "R10") (pin "1") (pinfunction "1_1") (pintype "passive"))
      (node (ref "R27") (pin "1") (pinfunction "1_1") (pintype "passive"))
      (node (ref "R28") (pin "1") (pinfunction "1_1") (pintype "passive"))
      (node (ref "R9") (pin "1") (pinfunction "1_1") (pintype "passive"))
      (node (ref "TP21") (pin "1") (pinfunction "TP_1") (pintype "passive"))
      (node (ref "TP22") (pin "1") (pinfunction "TP_1") (pintype "passive"))
      (node (ref "TP7") (pin "1") (pinfunction "TP_1") (pintype "passive"))
      (node (ref "TP8") (pin "1") (pinfunction "TP_1") (pintype "passive"))
    )
    (net (code "9") (name "/VOLTAGE_SENSE1-") (class "Default")
      (node (ref "C1") (pin "2") (pinfunction "2_2") (pintype "passive"))
      (node (ref "C2") (pin "2") (pinfunction "2_2") (pintype "passive"))
      (node (ref "C5") (pin "2") (pinfunction "2_2") (pintype "passive"))
      (node (ref "C6") (pin "2") (pinfunction "2_2") (pintype "passive"))
      (node (ref "J15") (pin "3") (pinfunction "3_3") (pintype "passive"))
      (node (ref "J16") (pin "3") (pinfunction "3_3") (pintype "passive"))
      (node (ref "J7") (pin "3") (pinfunction "3_3") (pintype "passive"))
      (node (ref "J8") (pin "3") (pinfunction "3_3") (pintype "passive"))
      (node (ref "R17") (pin "1") (pinfunction "1_1") (pintype "passive"))
      (node (ref "R18") (pin "1") (pinfunction "1_1") (pintype "passive"))
      (node (ref "R35") (pin "1") (pinfunction "1_1") (pintype "passive"))
      (node (ref "R36") (pin "1") (pinfunction "1_1") (pintype "passive"))
    )
    (net (code "10") (name "Net-(D1-ANODE)") (class "Default")
      (node (ref "D1") (pin "A") (pinfunction "ANODE_A") (pintype "passive"))
      (node (ref "J5") (pin "1") (pinfunction "1_1") (pintype "passive"))
      (node (ref "J5") (pin "2") (pinfunction "2_2") (pintype "passive"))
      (node (ref "J5") (pin "3") (pinfunction "3_3") (pintype "passive"))
      (node (ref "R1") (pin "1") (pinfunction "1_1") (pintype "passive"))
      (node (ref "R11") (pin "1") (pinfunction "1_1") (pintype "passive"))
      (node (ref "R17") (pin "2") (pinfunction "2_2") (pintype "passive"))
      (node (ref "R7") (pin "I2") (pinfunction "I2_I2") (pintype "passive"))
      (node (ref "TP4") (pin "1") (pinfunction "TP_1") (pintype "passive"))
    )
    (net (code "11") (name "Net-(D2-ANODE)") (class "Default")
      (node (ref "D2") (pin "A") (pinfunction "ANODE_A") (pintype "passive"))
      (node (ref "J6") (pin "1") (pinfunction "1_1") (pintype "passive"))
      (node (ref "J6") (pin "2") (pinfunction "2_2") (pintype "passive"))
      (node (ref "J6") (pin "3") (pinfunction "3_3") (pintype "passive"))
      (node (ref "R12") (pin "1") (pinfunction "1_1") (pintype "passive"))
      (node (ref "R18") (pin "2") (pinfunction "2_2") (pintype "passive"))
      (node (ref "R3") (pin "1") (pinfunction "1_1") (pintype "passive"))
      (node (ref "R8") (pin "I2") (pinfunction "I2_I2") (pintype "passive"))
      (node (ref "TP6") (pin "1") (pinfunction "TP_1") (pintype "passive"))
    )
    (net (code "12") (name "Net-(D3-ANODE)") (class "Default")
      (node (ref "D3") (pin "A") (pinfunction "ANODE_A") (pintype "passive"))
      (node (ref "J13") (pin "1") (pinfunction "1_1") (pintype "passive"))
      (node (ref "J13") (pin "2") (pinfunction "2_2") (pintype "passive"))
      (node (ref "J13") (pin "3") (pinfunction "3_3") (pintype "passive"))
      (node (ref "R19") (pin "1") (pinfunction "1_1") (pintype "passive"))
      (node (ref "R25") (pin "I2") (pinfunction "I2_I2") (pintype "passive"))
      (node (ref "R29") (pin "1") (pinfunction "1_1") (pintype "passive"))
      (node (ref "R35") (pin "2") (pinfunction "2_2") (pintype "passive"))
      (node (ref "TP18") (pin "1") (pinfunction "TP_1") (pintype "passive"))
    )
    (net (code "13") (name "Net-(D4-ANODE)") (class "Default")
      (node (ref "D4") (pin "A") (pinfunction "ANODE_A") (pintype "passive"))
      (node (ref "J14") (pin "1") (pinfunction "1_1") (pintype "passive"))
      (node (ref "J14") (pin "2") (pinfunction "2_2") (pintype "passive"))
      (node (ref "J14") (pin "3") (pinfunction "3_3") (pintype "passive"))
      (node (ref "R21") (pin "1") (pinfunction "1_1") (pintype "passive"))
      (node (ref "R26") (pin "I2") (pinfunction "I2_I2") (pintype "passive"))
      (node (ref "R30") (pin "1") (pinfunction "1_1") (pintype "passive"))
      (node (ref "R36") (pin "2") (pinfunction "2_2") (pintype "passive"))
      (node (ref "TP20") (pin "1") (pinfunction "TP_1") (pintype "passive"))
    )
    (net (code "14") (name "Net-(R10-Pad2)") (class "Default")
      (node (ref "R10") (pin "2") (pinfunction "2_2") (pintype "passive"))
      (node (ref "R12") (pin "2") (pinfunction "2_2") (pintype "passive"))
      (node (ref "R6") (pin "1") (pinfunction "1_1") (pintype "passive"))
    )
    (net (code "15") (name "Net-(R11-Pad2)") (class "Default")
      (node (ref "R11") (pin "2") (pinfunction "2_2") (pintype "passive"))
      (node (ref "R5") (pin "1") (pinfunction "1_1") (pintype "passive"))
      (node (ref "R9") (pin "2") (pinfunction "2_2") (pintype "passive"))
    )
    (net (code "16") (name "Net-(R13-Pad1)") (class "Default")
      (node (ref "R13") (pin "1") (pinfunction "1_1") (pintype "passive"))
      (node (ref "R7") (pin "E1") (pinfunction "E1_E1") (pintype "passive"))
    )
    (net (code "17") (name "Net-(R14-Pad1)") (class "Default")
      (node (ref "R14") (pin "1") (pinfunction "1_1") (pintype "passive"))
      (node (ref "R7") (pin "E2") (pinfunction "E2_E2") (pintype "passive"))
    )
    (net (code "18") (name "Net-(R15-Pad1)") (class "Default")
      (node (ref "R15") (pin "1") (pinfunction "1_1") (pintype "passive"))
      (node (ref "R8") (pin "E1") (pinfunction "E1_E1") (pintype "passive"))
    )
    (net (code "19") (name "Net-(R16-Pad1)") (class "Default")
      (node (ref "R16") (pin "1") (pinfunction "1_1") (pintype "passive"))
      (node (ref "R8") (pin "E2") (pinfunction "E2_E2") (pintype "passive"))
    )
    (net (code "20") (name "Net-(R23-Pad1)") (class "Default")
      (node (ref "R23") (pin "1") (pinfunction "1_1") (pintype "passive"))
      (node (ref "R27") (pin "2") (pinfunction "2_2") (pintype "passive"))
      (node (ref "R29") (pin "2") (pinfunction "2_2") (pintype "passive"))
    )
    (net (code "21") (name "Net-(R24-Pad1)") (class "Default")
      (node (ref "R24") (pin "1") (pinfunction "1_1") (pintype "passive"))
      (node (ref "R28") (pin "2") (pinfunction "2_2") (pintype "passive"))
      (node (ref "R30") (pin "2") (pinfunction "2_2") (pintype "passive"))
    )
    (net (code "22") (name "Net-(R25-PadE1)") (class "Default")
      (node (ref "R25") (pin "E1") (pinfunction "E1_E1") (pintype "passive"))
      (node (ref "R31") (pin "1") (pinfunction "1_1") (pintype "passive"))
    )
    (net (code "23") (name "Net-(R25-PadE2)") (class "Default")
      (node (ref "R25") (pin "E2") (pinfunction "E2_E2") (pintype "passive"))
      (node (ref "R32") (pin "1") (pinfunction "1_1") (pintype "passive"))
    )
    (net (code "24") (name "Net-(R26-PadE1)") (class "Default")
      (node (ref "R26") (pin "E1") (pinfunction "E1_E1") (pintype "passive"))
      (node (ref "R33") (pin "1") (pinfunction "1_1") (pintype "passive"))
    )
    (net (code "25") (name "Net-(R26-PadE2)") (class "Default")
      (node (ref "R26") (pin "E2") (pinfunction "E2_E2") (pintype "passive"))
      (node (ref "R34") (pin "1") (pinfunction "1_1") (pintype "passive"))
    )
    (net (code "26") (name "unconnected-(MT1-CENTER-Pad1)") (class "Default")
      (node (ref "MT1") (pin "1") (pinfunction "CENTER_1") (pintype "passive+no_connect"))
    )
    (net (code "27") (name "unconnected-(MT2-CENTER-Pad1)") (class "Default")
      (node (ref "MT2") (pin "1") (pinfunction "CENTER_1") (pintype "passive+no_connect"))
    )
    (net (code "28") (name "unconnected-(MT3-CENTER-Pad1)") (class "Default")
      (node (ref "MT3") (pin "1") (pinfunction "CENTER_1") (pintype "passive+no_connect"))
    )
    (net (code "29") (name "unconnected-(MT4-CENTER-Pad1)") (class "Default")
      (node (ref "MT4") (pin "1") (pinfunction "CENTER_1") (pintype "passive+no_connect"))
    )
    (net (code "30") (name "unconnected-(MT5-CENTER-Pad1)") (class "Default")
      (node (ref "MT5") (pin "1") (pinfunction "CENTER_1") (pintype "passive+no_connect"))
    )
    (net (code "31") (name "unconnected-(MT6-CENTER-Pad1)") (class "Default")
      (node (ref "MT6") (pin "1") (pinfunction "CENTER_1") (pintype "passive+no_connect"))
    )
  )
)
